# esp32_LoRa_relay_pump.net
KiCad netlist of a schematic drawn in EAGLE
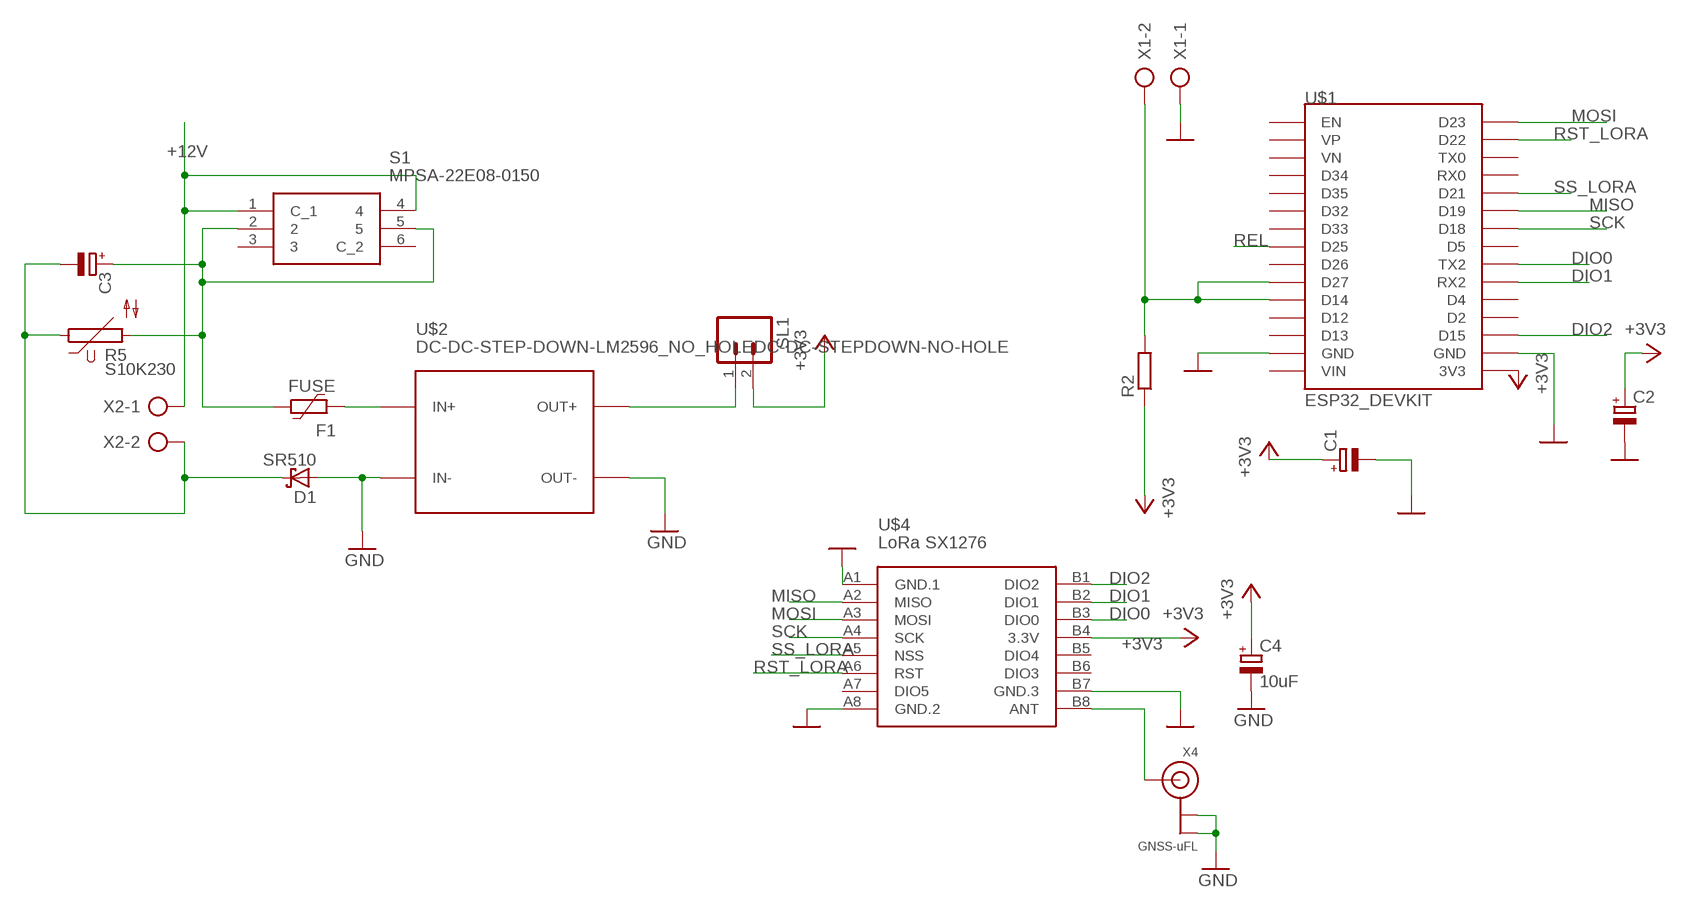
[diagram p0: schematic, sheet 1]
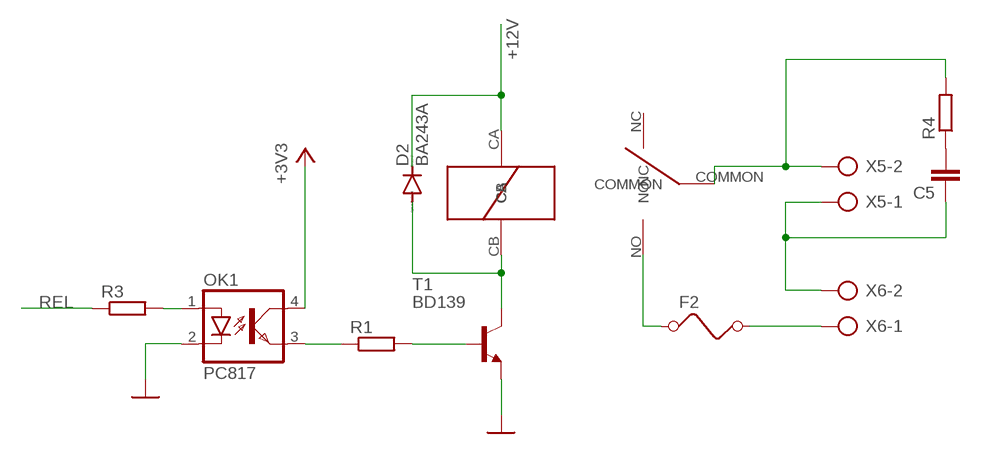
[diagram p1: schematic, sheet 2]

(export (version "E")
  (design (tool "Eeschema 10.0.6"))
  (components
    (comp (ref "C5")
      (value "C-EU150-064X183")
      (footprint "eagle-import:C150-064X183")
      (libsource (lib "eagle-import") (part "C-EU150-064X183"))
    )
    (comp (ref "D2")
      (value "BA243A")
      (footprint "eagle-import:DO35-10")
      (libsource (lib "eagle-import") (part "BA243A"))
    )
    (comp (ref "F2")
      (value "FUSE")
      (footprint "eagle-import:FUSE")
      (libsource (lib "eagle-import") (part "FUSE"))
    )
    (comp (ref "OK1")
      (value "PC817")
      (footprint "eagle-import:DIL04")
      (fields (field (name "MPN") "PC817X4J000F"))
      (libsource (lib "eagle-import") (part "PC817"))
    )
    (comp (ref "R1")
      (value "R-EU_M0805")
      (footprint "eagle-import:M0805")
      (libsource (lib "eagle-import") (part "R-EU_M0805"))
    )
    (comp (ref "R3")
      (value "R-EU_M0805")
      (footprint "eagle-import:M0805")
      (libsource (lib "eagle-import") (part "R-EU_M0805"))
    )
    (comp (ref "R4")
      (value "R-EU_0817/7V")
      (footprint "eagle-import:P0817V")
      (libsource (lib "eagle-import") (part "R-EU_0817/7V"))
    )
    (comp (ref "T1")
      (value "BD139")
      (footprint "eagle-import:TO126")
      (libsource (lib "eagle-import") (part "BD139"))
    )
    (comp (ref "U$3")
      (value "SONGLE_30A")
      (footprint "eagle-import:RELAY_SONGLE_4PIN")
      (libsource (lib "eagle-import") (part "SONGLE_30A"))
    )
    (comp (ref "X5")
      (value "AK300/2")
      (footprint "eagle-import:AK300_2")
      (libsource (lib "eagle-import") (part "AK300/2"))
    )
    (comp (ref "X6")
      (value "AK300/2")
      (footprint "eagle-import:AK300_2")
      (libsource (lib "eagle-import") (part "AK300/2"))
    )
    (comp (ref "C1")
      (value "CPOL-EUE5-8.5")
      (footprint "eagle-import:E5-8,5")
      (libsource (lib "eagle-import") (part "CPOL-EUE5-8.5"))
    )
    (comp (ref "C2")
      (value "CPOL-EUE5-8.5")
      (footprint "eagle-import:E5-8,5")
      (libsource (lib "eagle-import") (part "CPOL-EUE5-8.5"))
    )
    (comp (ref "C3")
      (value "CPOL-EUE5-13")
      (footprint "eagle-import:E5-13")
      (libsource (lib "eagle-import") (part "CPOL-EUE5-13"))
    )
    (comp (ref "C4")
      (value "10uF")
      (footprint "eagle-import:E2,5-6")
      (libsource (lib "eagle-import") (part "CPOL-EUE2.5-6"))
    )
    (comp (ref "D1")
      (value "SR510")
      (footprint "eagle-import:SMB")
      (libsource (lib "eagle-import") (part "SCHOTTKY-DIODESMD"))
    )
    (comp (ref "F1")
      (value "FUSE")
      (footprint "eagle-import:1812L")
      (fields (field (name "MF") "Littelfuse") (field (name "MPN") "1812L010"))
      (libsource (lib "eagle-import") (part "?1812L010"))
    )
    (comp (ref "R2")
      (value "R-EU_0309/12")
      (footprint "eagle-import:0309_12")
      (libsource (lib "eagle-import") (part "R-EU_0309/12"))
    )
    (comp (ref "R5")
      (value "S10K230")
      (footprint "eagle-import:S10K230")
      (libsource (lib "eagle-import") (part "S10K230"))
    )
    (comp (ref "S1")
      (value "MPSA-22E08-0150")
      (footprint "eagle-import:MPSA22E080150")
      (fields (field (name "RS_PART_NUMBER") "9138895"))
      (libsource (lib "eagle-import") (part "MPSA-22E08-0150"))
    )
    (comp (ref "SL1")
      (value "M02")
      (footprint "eagle-import:02P")
      (libsource (lib "eagle-import") (part "M02"))
    )
    (comp (ref "U$1")
      (value "ESP32_DEVKIT")
      (footprint "eagle-import:ESP32_DEVKIT")
      (libsource (lib "eagle-import") (part "ESP32_DEVKIT"))
    )
    (comp (ref "U$2")
      (value "DC-DC-STEP-DOWN-LM2596_NO_HOLEDC-DC-STEPDOWN-NO-HOLE")
      (footprint "eagle-import:DC-DC-STEP-DOWN-LM2596_NO_HOLE")
      (libsource (lib "eagle-import") (part "DC-DC-STEP-DOWN-LM2596_NO_HOLEDC-DC-STEPDOWN-NO-HOLE"))
    )
    (comp (ref "U$4")
      (value "LoRa SX1276")
      (footprint "eagle-import:WIRELESS-LORA-RFM95W#SMD")
      (libsource (lib "eagle-import") (part "WIRELESS-LORA-RFM95W#SMD"))
    )
    (comp (ref "X1")
      (value "AK300/2")
      (footprint "eagle-import:AK300_2")
      (libsource (lib "eagle-import") (part "AK300/2"))
    )
    (comp (ref "X2")
      (value "AK300/2")
      (footprint "eagle-import:AK300_2")
      (libsource (lib "eagle-import") (part "AK300/2"))
    )
    (comp (ref "X4")
      (value "GNSS-uFL")
      (footprint "eagle-import:U.FL")
      (libsource (lib "eagle-import") (part "ANTENNA_U.FL"))
    )
  )
  (nets
    (net (code "1") (name "+3V3") (class "Default")
      (node (ref "C1") (pin "+") (pinfunction "+_+") (pintype "passive"))
      (node (ref "C2") (pin "+") (pinfunction "+_+") (pintype "passive"))
      (node (ref "C4") (pin "+") (pinfunction "+_+") (pintype "passive"))
      (node (ref "OK1") (pin "4") (pinfunction "COL_4") (pintype "passive"))
      (node (ref "R2") (pin "1") (pinfunction "1_1") (pintype "passive"))
      (node (ref "SL1") (pin "2") (pinfunction "2_2") (pintype "passive"))
      (node (ref "U$1") (pin "3V3") (pinfunction "3V3_3V3") (pintype "bidirectional"))
      (node (ref "U$4") (pin "B4") (pinfunction "3.3V_B4") (pintype "power_in"))
    )
    (net (code "2") (name "+12V") (class "Default")
      (node (ref "D2") (pin "C") (pinfunction "C_C") (pintype "passive"))
      (node (ref "S1") (pin "1") (pinfunction "C_1_1") (pintype "bidirectional"))
      (node (ref "S1") (pin "4") (pinfunction "4_4") (pintype "bidirectional"))
      (node (ref "U$3") (pin "CA") (pinfunction "CA_CA") (pintype "bidirectional"))
      (node (ref "X2") (pin "1") (pinfunction "KL_1") (pintype "passive"))
    )
    (net (code "3") (name "DIO0") (class "Default")
      (node (ref "U$1") (pin "TX2") (pinfunction "TX2_TX2") (pintype "bidirectional"))
      (node (ref "U$4") (pin "B3") (pinfunction "DIO0_B3") (pintype "bidirectional"))
    )
    (net (code "4") (name "DIO1") (class "Default")
      (node (ref "U$1") (pin "RX2") (pinfunction "RX2_RX2") (pintype "bidirectional"))
      (node (ref "U$4") (pin "B2") (pinfunction "DIO1_B2") (pintype "bidirectional"))
    )
    (net (code "5") (name "DIO2") (class "Default")
      (node (ref "U$1") (pin "D15") (pinfunction "D15_D15") (pintype "bidirectional"))
      (node (ref "U$4") (pin "B1") (pinfunction "DIO2_B1") (pintype "bidirectional"))
    )
    (net (code "6") (name "GND") (class "Default")
      (node (ref "C1") (pin "-") (pinfunction "-_-") (pintype "passive"))
      (node (ref "C2") (pin "-") (pinfunction "-_-") (pintype "passive"))
      (node (ref "C4") (pin "-") (pinfunction "-_-") (pintype "passive"))
      (node (ref "D1") (pin "A") (pinfunction "A_A") (pintype "passive"))
      (node (ref "OK1") (pin "2") (pinfunction "C_2") (pintype "passive"))
      (node (ref "T1") (pin "1") (pinfunction "E_1") (pintype "passive"))
      (node (ref "U$1") (pin "GND@1") (pinfunction "GND_GND@1") (pintype "bidirectional"))
      (node (ref "U$1") (pin "GND@2") (pinfunction "GND_GND@2") (pintype "bidirectional"))
      (node (ref "U$2") (pin "IN-") (pinfunction "IN-_IN-") (pintype "bidirectional"))
      (node (ref "U$2") (pin "OUT-") (pinfunction "OUT-_OUT-") (pintype "bidirectional"))
      (node (ref "U$4") (pin "A1") (pinfunction "GND.1_A1") (pintype "power_in"))
      (node (ref "U$4") (pin "A8") (pinfunction "GND.2_A8") (pintype "power_in"))
      (node (ref "U$4") (pin "B7") (pinfunction "GND.3_B7") (pintype "power_in"))
      (node (ref "X1") (pin "1") (pinfunction "KL_1") (pintype "passive"))
      (node (ref "X4") (pin "1") (pinfunction "GND_1") (pintype "passive"))
      (node (ref "X4") (pin "2") (pinfunction "GND_2") (pintype "passive"))
    )
    (net (code "7") (name "MISO") (class "Default")
      (node (ref "U$1") (pin "D19") (pinfunction "D19_D19") (pintype "bidirectional"))
      (node (ref "U$4") (pin "A2") (pinfunction "MISO_A2") (pintype "bidirectional"))
    )
    (net (code "8") (name "MOSI") (class "Default")
      (node (ref "U$1") (pin "D23") (pinfunction "D23_D23") (pintype "bidirectional"))
      (node (ref "U$4") (pin "A3") (pinfunction "MOSI_A3") (pintype "bidirectional"))
    )
    (net (code "9") (name "Net-(C3-Pad+)") (class "Default")
      (node (ref "C3") (pin "+") (pinfunction "+_+") (pintype "passive"))
      (node (ref "F1") (pin "1") (pinfunction "1_1") (pintype "passive"))
      (node (ref "R5") (pin "2") (pinfunction "2_2") (pintype "passive"))
      (node (ref "S1") (pin "2") (pinfunction "2_2") (pintype "bidirectional"))
      (node (ref "S1") (pin "5") (pinfunction "5_5") (pintype "bidirectional"))
    )
    (net (code "10") (name "Net-(C5-Pad2)") (class "Default")
      (node (ref "C5") (pin "2") (pinfunction "2_2") (pintype "passive"))
      (node (ref "R4") (pin "1") (pinfunction "1_1") (pintype "passive"))
    )
    (net (code "11") (name "Net-(F1-Pad2)") (class "Default")
      (node (ref "F1") (pin "2") (pinfunction "2_2") (pintype "passive"))
      (node (ref "U$2") (pin "IN+") (pinfunction "IN+_IN+") (pintype "bidirectional"))
    )
    (net (code "12") (name "Net-(F2-Pad1)") (class "Default")
      (node (ref "F2") (pin "1") (pinfunction "1_1") (pintype "passive"))
      (node (ref "U$3") (pin "NO") (pinfunction "NO_NO") (pintype "bidirectional"))
    )
    (net (code "13") (name "Net-(OK1-A)") (class "Default")
      (node (ref "OK1") (pin "1") (pinfunction "A_1") (pintype "passive"))
      (node (ref "R3") (pin "2") (pinfunction "2_2") (pintype "passive"))
    )
    (net (code "14") (name "Net-(OK1-EMIT)") (class "Default")
      (node (ref "OK1") (pin "3") (pinfunction "EMIT_3") (pintype "passive"))
      (node (ref "R1") (pin "1") (pinfunction "1_1") (pintype "passive"))
    )
    (net (code "15") (name "Net-(SL1-Pad1)") (class "Default")
      (node (ref "SL1") (pin "1") (pinfunction "1_1") (pintype "passive"))
      (node (ref "U$2") (pin "OUT+") (pinfunction "OUT+_OUT+") (pintype "bidirectional"))
    )
    (net (code "16") (name "Net-(T1-B)") (class "Default")
      (node (ref "R1") (pin "2") (pinfunction "2_2") (pintype "passive"))
      (node (ref "T1") (pin "3") (pinfunction "B_3") (pintype "passive"))
    )
    (net (code "17") (name "Net-(T1-C)") (class "Default")
      (node (ref "D2") (pin "A") (pinfunction "A_A") (pintype "passive"))
      (node (ref "T1") (pin "2") (pinfunction "C_2") (pintype "passive"))
      (node (ref "U$3") (pin "CB") (pinfunction "CB_CB") (pintype "bidirectional"))
    )
    (net (code "18") (name "Net-(U$4-ANT)") (class "Default")
      (node (ref "U$4") (pin "B8") (pinfunction "ANT_B8") (pintype "passive"))
      (node (ref "X4") (pin "3") (pinfunction "SIGNAL_3") (pintype "passive"))
    )
    (net (code "19") (name "Net-(X1B-KL)") (class "Default")
      (node (ref "R2") (pin "2") (pinfunction "2_2") (pintype "passive"))
      (node (ref "U$1") (pin "D14") (pinfunction "D14_D14") (pintype "bidirectional"))
      (node (ref "U$1") (pin "D27") (pinfunction "D27_D27") (pintype "bidirectional"))
      (node (ref "X1") (pin "2") (pinfunction "KL_2") (pintype "passive"))
    )
    (net (code "20") (name "Net-(X2B-KL)") (class "Default")
      (node (ref "C3") (pin "-") (pinfunction "-_-") (pintype "passive"))
      (node (ref "D1") (pin "C") (pinfunction "C_C") (pintype "passive"))
      (node (ref "R5") (pin "1") (pinfunction "1_1") (pintype "passive"))
      (node (ref "X2") (pin "2") (pinfunction "KL_2") (pintype "passive"))
    )
    (net (code "21") (name "Net-(X5A-KL)") (class "Default")
      (node (ref "C5") (pin "1") (pinfunction "1_1") (pintype "passive"))
      (node (ref "X5") (pin "1") (pinfunction "KL_1") (pintype "passive"))
      (node (ref "X6") (pin "2") (pinfunction "KL_2") (pintype "passive"))
    )
    (net (code "22") (name "Net-(X5B-KL)") (class "Default")
      (node (ref "R4") (pin "2") (pinfunction "2_2") (pintype "passive"))
      (node (ref "U$3") (pin "COMMON") (pinfunction "COMMON_COMMON") (pintype "bidirectional"))
      (node (ref "X5") (pin "2") (pinfunction "KL_2") (pintype "passive"))
    )
    (net (code "23") (name "Net-(X6A-KL)") (class "Default")
      (node (ref "F2") (pin "2") (pinfunction "2_2") (pintype "passive"))
      (node (ref "X6") (pin "1") (pinfunction "KL_1") (pintype "passive"))
    )
    (net (code "24") (name "REL") (class "Default")
      (node (ref "R3") (pin "1") (pinfunction "1_1") (pintype "passive"))
      (node (ref "U$1") (pin "D25") (pinfunction "D25_D25") (pintype "bidirectional"))
    )
    (net (code "25") (name "RST_LORA") (class "Default")
      (node (ref "U$1") (pin "D22") (pinfunction "D22_D22") (pintype "bidirectional"))
      (node (ref "U$4") (pin "A6") (pinfunction "RST_A6") (pintype "bidirectional"))
    )
    (net (code "26") (name "SCK") (class "Default")
      (node (ref "U$1") (pin "D18") (pinfunction "D18_D18") (pintype "bidirectional"))
      (node (ref "U$4") (pin "A4") (pinfunction "SCK_A4") (pintype "bidirectional"))
    )
    (net (code "27") (name "SS_LORA") (class "Default")
      (node (ref "U$1") (pin "D21") (pinfunction "D21_D21") (pintype "bidirectional"))
      (node (ref "U$4") (pin "A5") (pinfunction "NSS_A5") (pintype "bidirectional"))
    )
    (net (code "28") (name "unconnected-(S1-C_2-Pad6)") (class "Default")
      (node (ref "S1") (pin "6") (pinfunction "C_2_6") (pintype "bidirectional"))
    )
    (net (code "29") (name "unconnected-(S1-Pad3)") (class "Default")
      (node (ref "S1") (pin "3") (pinfunction "3_3") (pintype "bidirectional"))
    )
    (net (code "30") (name "unconnected-(U$1-PadD2)") (class "Default")
      (node (ref "U$1") (pin "D2") (pinfunction "D2_D2") (pintype "bidirectional"))
    )
    (net (code "31") (name "unconnected-(U$1-PadD4)") (class "Default")
      (node (ref "U$1") (pin "D4") (pinfunction "D4_D4") (pintype "bidirectional"))
    )
    (net (code "32") (name "unconnected-(U$1-PadD5)") (class "Default")
      (node (ref "U$1") (pin "D5") (pinfunction "D5_D5") (pintype "bidirectional"))
    )
    (net (code "33") (name "unconnected-(U$1-PadD12)") (class "Default")
      (node (ref "U$1") (pin "D12") (pinfunction "D12_D12") (pintype "bidirectional"))
    )
    (net (code "34") (name "unconnected-(U$1-PadD13)") (class "Default")
      (node (ref "U$1") (pin "D13") (pinfunction "D13_D13") (pintype "bidirectional"))
    )
    (net (code "35") (name "unconnected-(U$1-PadD26)") (class "Default")
      (node (ref "U$1") (pin "D26") (pinfunction "D26_D26") (pintype "bidirectional"))
    )
    (net (code "36") (name "unconnected-(U$1-PadD32)") (class "Default")
      (node (ref "U$1") (pin "D32") (pinfunction "D32_D32") (pintype "bidirectional"))
    )
    (net (code "37") (name "unconnected-(U$1-PadD33)") (class "Default")
      (node (ref "U$1") (pin "D33") (pinfunction "D33_D33") (pintype "bidirectional"))
    )
    (net (code "38") (name "unconnected-(U$1-PadD34)") (class "Default")
      (node (ref "U$1") (pin "D34") (pinfunction "D34_D34") (pintype "bidirectional"))
    )
    (net (code "39") (name "unconnected-(U$1-PadD35)") (class "Default")
      (node (ref "U$1") (pin "D35") (pinfunction "D35_D35") (pintype "bidirectional"))
    )
    (net (code "40") (name "unconnected-(U$1-PadEN)") (class "Default")
      (node (ref "U$1") (pin "EN") (pinfunction "EN_EN") (pintype "bidirectional"))
    )
    (net (code "41") (name "unconnected-(U$1-PadRX0)") (class "Default")
      (node (ref "U$1") (pin "RX0") (pinfunction "RX0_RX0") (pintype "bidirectional"))
    )
    (net (code "42") (name "unconnected-(U$1-PadTX0)") (class "Default")
      (node (ref "U$1") (pin "TX0") (pinfunction "TX0_TX0") (pintype "bidirectional"))
    )
    (net (code "43") (name "unconnected-(U$1-PadVIN)") (class "Default")
      (node (ref "U$1") (pin "VIN") (pinfunction "VIN_VIN") (pintype "bidirectional"))
    )
    (net (code "44") (name "unconnected-(U$1-PadVN)") (class "Default")
      (node (ref "U$1") (pin "VN") (pinfunction "VN_VN") (pintype "bidirectional"))
    )
    (net (code "45") (name "unconnected-(U$1-PadVP)") (class "Default")
      (node (ref "U$1") (pin "VP") (pinfunction "VP_VP") (pintype "bidirectional"))
    )
    (net (code "46") (name "unconnected-(U$3-PadNC)") (class "Default")
      (node (ref "U$3") (pin "NC") (pinfunction "NC_NC") (pintype "bidirectional"))
    )
    (net (code "47") (name "unconnected-(U$4-DIO3-PadB6)") (class "Default")
      (node (ref "U$4") (pin "B6") (pinfunction "DIO3_B6") (pintype "bidirectional"))
    )
    (net (code "48") (name "unconnected-(U$4-DIO4-PadB5)") (class "Default")
      (node (ref "U$4") (pin "B5") (pinfunction "DIO4_B5") (pintype "bidirectional"))
    )
    (net (code "49") (name "unconnected-(U$4-DIO5-PadA7)") (class "Default")
      (node (ref "U$4") (pin "A7") (pinfunction "DIO5_A7") (pintype "bidirectional"))
    )
  )
)
